# PA_MCU.net
KiCad netlist of a schematic drawn in Altium Designer
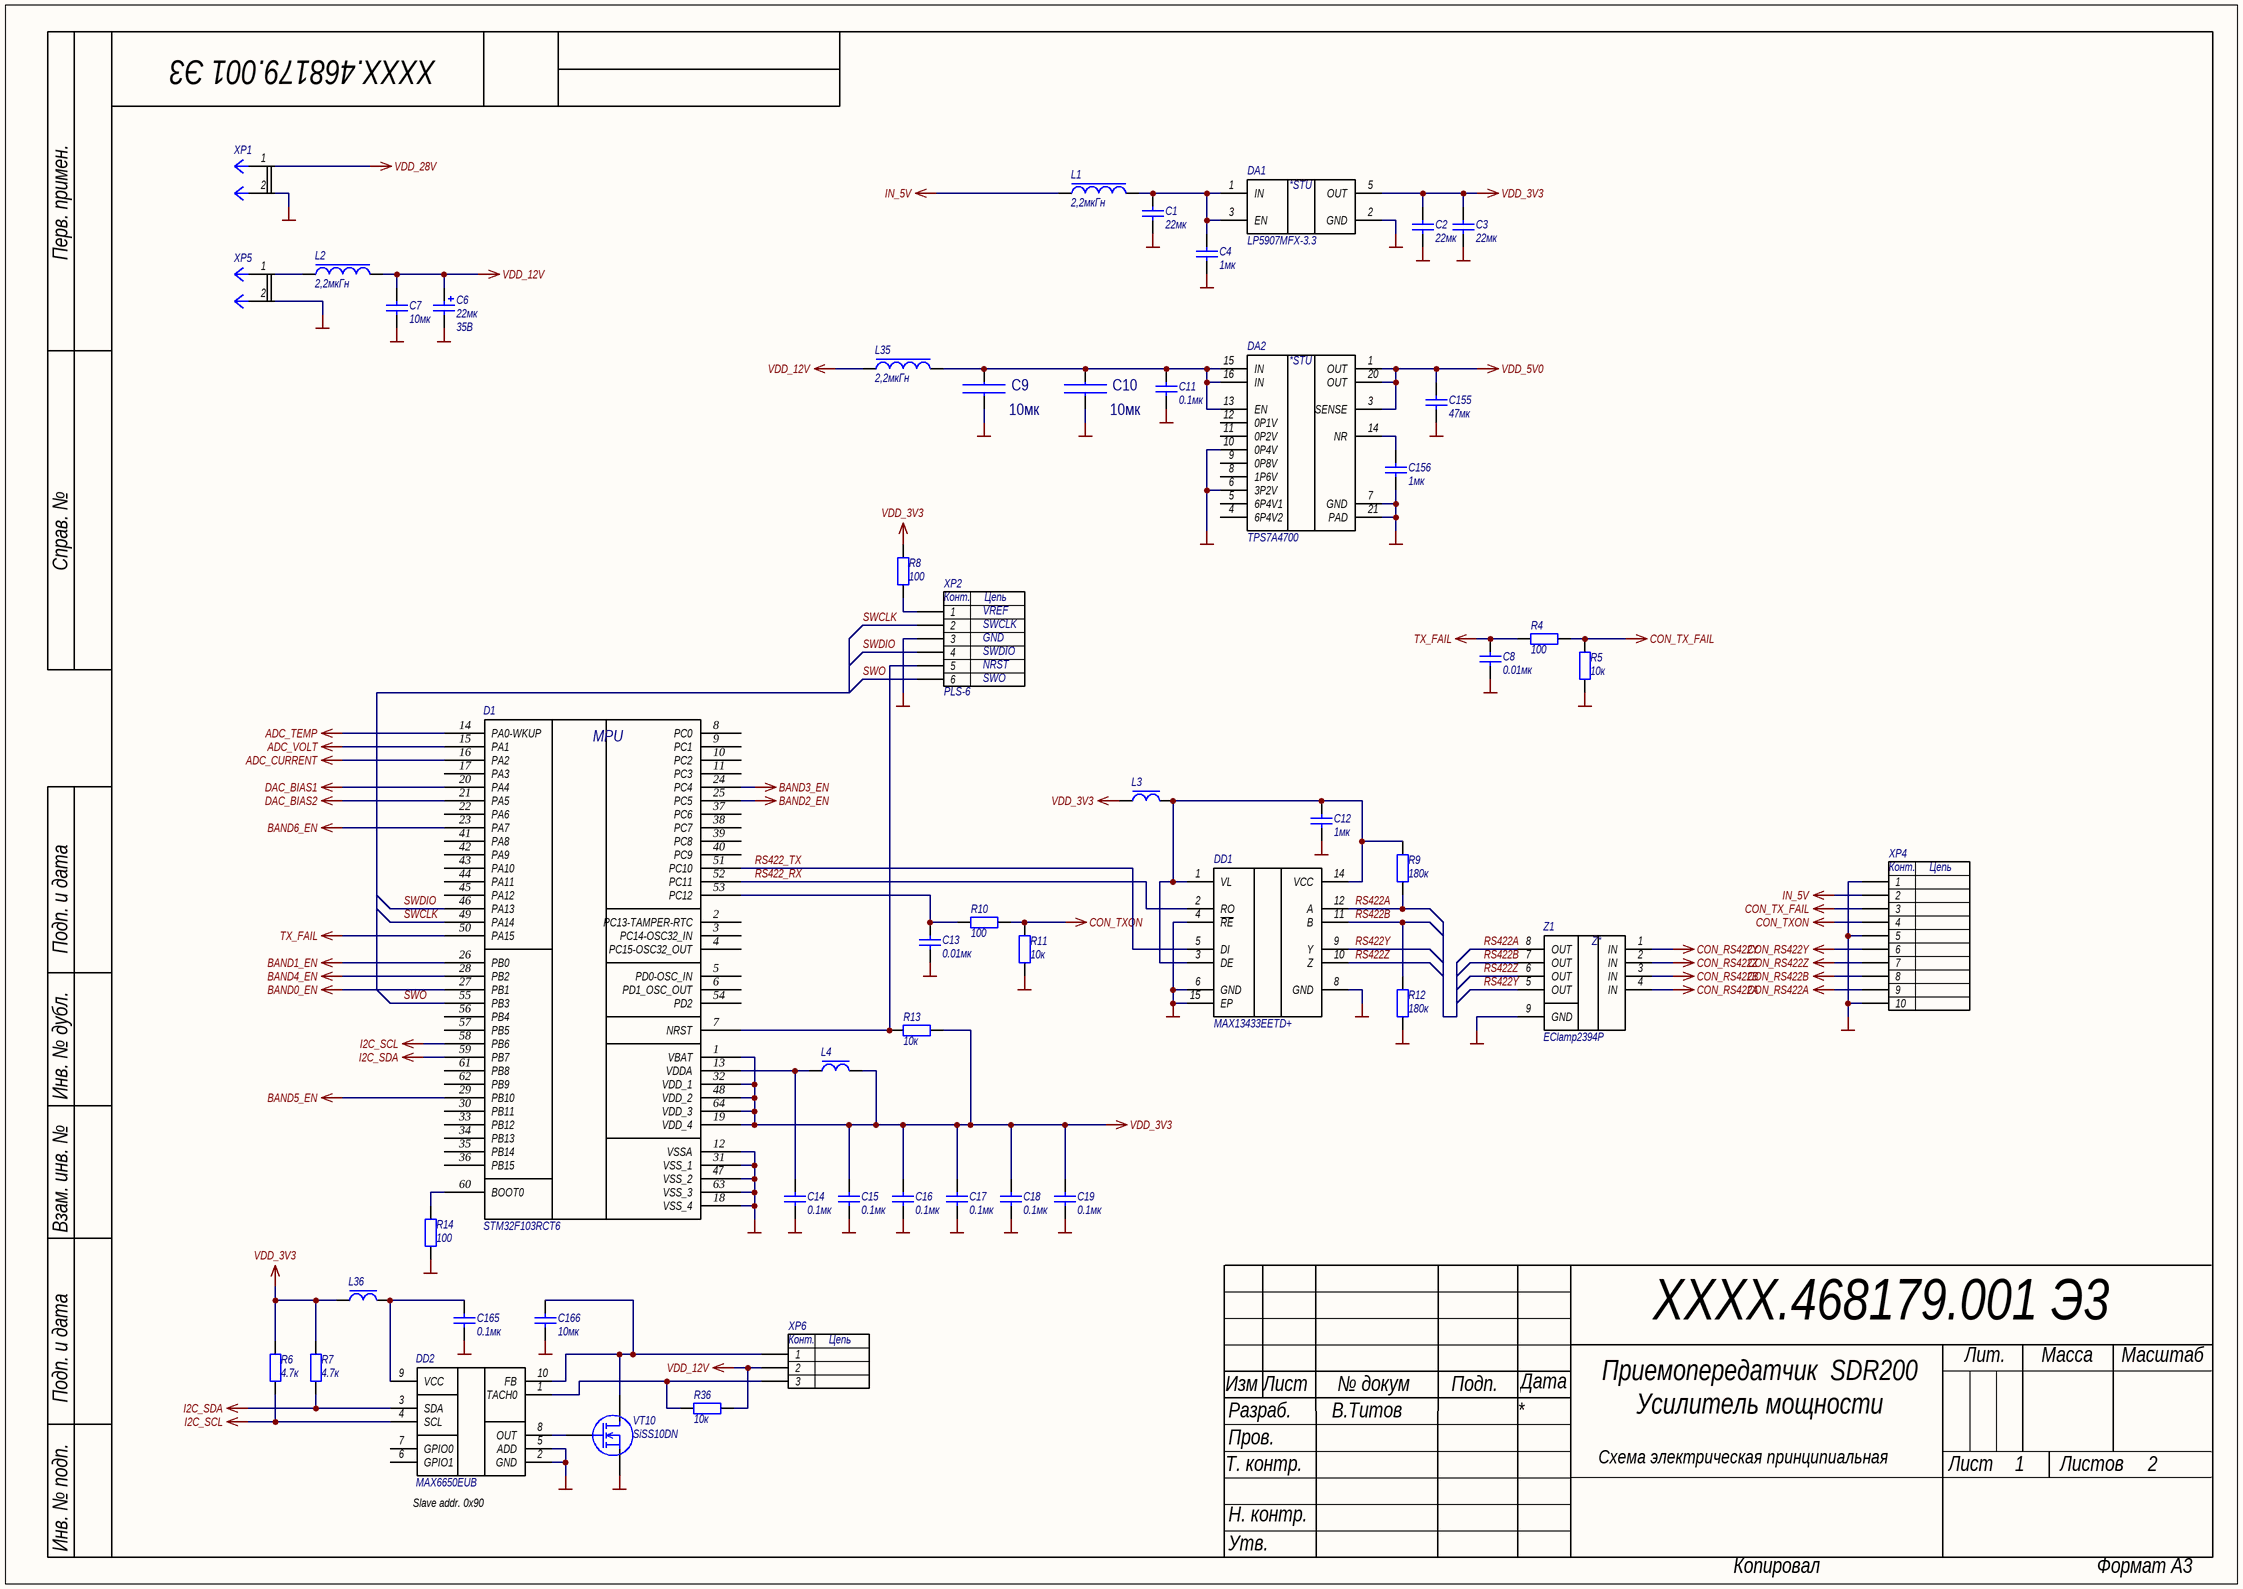
[diagram p0: PA_MCU.SchDoc]

(export (version "E")
  (design (tool "Eeschema 10.0.6"))
  (components
    (comp (ref "C1")
      (value "22мк")
      (footprint "CAPC2012X12L")
      (description "Кер. ЧИП-конденсатор")
      (fields (field (name "MANUFACTURER") "TDK") (field (name "TOLERANCE") "±10%"))
      (libsource (lib "nels_caps") (part "Кер.ЧИП конд. 0805 22мкФ X5R 10% 16В"))
    )
    (comp (ref "C2")
      (value "22мк")
      (footprint "CAPC2012X12L")
      (description "Кер. ЧИП-конденсатор")
      (fields (field (name "MANUFACTURER") "TDK") (field (name "TOLERANCE") "±10%"))
      (libsource (lib "nels_caps") (part "Кер.ЧИП конд. 0805 22мкФ X5R 10% 16В"))
    )
    (comp (ref "C3")
      (value "22мк")
      (footprint "CAPC2012X12L")
      (description "Кер. ЧИП-конденсатор")
      (fields (field (name "MANUFACTURER") "TDK") (field (name "TOLERANCE") "±10%"))
      (libsource (lib "nels_caps") (part "Кер.ЧИП конд. 0805 22мкФ X5R 10% 16В"))
    )
    (comp (ref "C4")
      (value "1мк")
      (footprint "CAPC1005X06N")
      (description "Кер. ЧИП-конденсатор")
      (fields (field (name "TOLERANCE") "±10%"))
      (libsource (lib "nels_caps") (part "Кер.ЧИП конд. 0402 1мкФ X5R 10%, 10В"))
    )
    (comp (ref "C6")
      (value "22мк")
      (footprint "CAPMP7343X28L")
      (description "Тант. ЧИП-конденсатор")
      (fields
        (field (name "TOLERANCE") "±20%")
        (field (name "POWER/VOLTAGE") "35В")
        (field (name "PUBLISHER") "Altium Limited")
      )
      (libsource (lib "nels_caps") (part "Конденсатор танталовый SMD D case 22мкФ ±20% 35B"))
    )
    (comp (ref "C7")
      (value "10мк")
      (footprint "CAPC3225X27L")
      (description "Кер. ЧИП-конденсатор")
      (fields (field (name "MANUFACTURER") "Murata") (field (name "TOLERANCE") "±20%"))
      (libsource (lib "nels_caps") (part "Кер.ЧИП конд. 1210 10мкФ X5R 20% 50В"))
    )
    (comp (ref "C8")
      (value "0.01мк")
      (footprint "CAPC1005X06N")
      (description "Кер. ЧИП-конденсатор")
      (fields (field (name "TOLERANCE") "±20%"))
      (libsource (lib "nels_caps") (part "Кер.ЧИП конд. 0402 0.01мкФ X7R 10%, 50В"))
    )
    (comp (ref "C9")
      (value "CC0805KKX5R8BB106")
      (footprint "CAPC2012X09L")
      (description "ЧИП конденсатор")
      (fields
        (field (name "MANUFACTURER") "Yageo")
        (field (name "TOLERANCE") "0,1")
        (field (name "NOMINAL") "10мк")
      )
      (libsource (lib "Database_Gost") (part "Capacitor const"))
    )
    (comp (ref "C10")
      (value "CC0805KKX5R8BB106")
      (footprint "CAPC2012X09L")
      (description "ЧИП конденсатор")
      (fields
        (field (name "MANUFACTURER") "Yageo")
        (field (name "TOLERANCE") "0,1")
        (field (name "NOMINAL") "10мк")
      )
      (libsource (lib "Database_Gost") (part "Capacitor const"))
    )
    (comp (ref "C11")
      (value "0.1мк")
      (footprint "CAPC1005X06N")
      (description "Кер. ЧИП-конденсатор")
      (fields (field (name "TOLERANCE") "±10%"))
      (libsource (lib "nels") (part "Кер.ЧИП конд. 0402 0.1мкФ X7R 10%, 16В"))
    )
    (comp (ref "C12")
      (value "1мк")
      (footprint "CAPC1005X06N")
      (description "Кер. ЧИП-конденсатор")
      (fields (field (name "TOLERANCE") "±10%"))
      (libsource (lib "nels_caps") (part "Кер.ЧИП конд. 0402 1мкФ X5R 10%, 10В"))
    )
    (comp (ref "C13")
      (value "0.01мк")
      (footprint "CAPC1005X06N")
      (description "Кер. ЧИП-конденсатор")
      (fields (field (name "TOLERANCE") "±20%"))
      (libsource (lib "nels_caps") (part "Кер.ЧИП конд. 0402 0.01мкФ X7R 10%, 50В"))
    )
    (comp (ref "C14")
      (value "0.1мк")
      (footprint "CAPC1005X06N")
      (description "Кер. ЧИП-конденсатор")
      (fields (field (name "TOLERANCE") "±10%"))
      (libsource (lib "nels") (part "Кер.ЧИП конд. 0402 0.1мкФ X7R 10%, 16В"))
    )
    (comp (ref "C15")
      (value "0.1мк")
      (footprint "CAPC1005X06N")
      (description "Кер. ЧИП-конденсатор")
      (fields (field (name "TOLERANCE") "±10%"))
      (libsource (lib "nels") (part "Кер.ЧИП конд. 0402 0.1мкФ X7R 10%, 16В"))
    )
    (comp (ref "C16")
      (value "0.1мк")
      (footprint "CAPC1005X06N")
      (description "Кер. ЧИП-конденсатор")
      (fields (field (name "TOLERANCE") "±10%"))
      (libsource (lib "nels") (part "Кер.ЧИП конд. 0402 0.1мкФ X7R 10%, 16В"))
    )
    (comp (ref "C17")
      (value "0.1мк")
      (footprint "CAPC1005X06N")
      (description "Кер. ЧИП-конденсатор")
      (fields (field (name "TOLERANCE") "±10%"))
      (libsource (lib "nels") (part "Кер.ЧИП конд. 0402 0.1мкФ X7R 10%, 16В"))
    )
    (comp (ref "C18")
      (value "0.1мк")
      (footprint "CAPC1005X06N")
      (description "Кер. ЧИП-конденсатор")
      (fields (field (name "TOLERANCE") "±10%"))
      (libsource (lib "nels") (part "Кер.ЧИП конд. 0402 0.1мкФ X7R 10%, 16В"))
    )
    (comp (ref "C19")
      (value "0.1мк")
      (footprint "CAPC1005X06N")
      (description "Кер. ЧИП-конденсатор")
      (fields (field (name "TOLERANCE") "±10%"))
      (libsource (lib "nels") (part "Кер.ЧИП конд. 0402 0.1мкФ X7R 10%, 16В"))
    )
    (comp (ref "C155")
      (value "47мк")
      (footprint "CAPC2012X12L")
      (description "Кер. ЧИП-конденсатор")
      (fields (field (name "MANUFACTURER") "Murata") (field (name "TOLERANCE") "±20%"))
      (libsource (lib "nels_caps") (part "Кер.ЧИП конд. 0805 47мкФ X5R 20% 10В"))
    )
    (comp (ref "C156")
      (value "1мк")
      (footprint "CAPC1005X06N")
      (description "Кер. ЧИП-конденсатор")
      (fields (field (name "TOLERANCE") "±10%"))
      (libsource (lib "nels_caps") (part "Кер.ЧИП конд. 0402 1мкФ X5R 10%, 10В"))
    )
    (comp (ref "C165")
      (value "0.1мк")
      (footprint "CAPC1005X06N")
      (description "Кер. ЧИП-конденсатор")
      (fields (field (name "TOLERANCE") "±10%"))
      (libsource (lib "nels") (part "Кер.ЧИП конд. 0402 0.1мкФ X7R 10%, 16В"))
    )
    (comp (ref "C166")
      (value "10мк")
      (footprint "CAPC3225X27L")
      (description "Кер. ЧИП-конденсатор")
      (fields (field (name "MANUFACTURER") "Murata") (field (name "TOLERANCE") "±20%"))
      (libsource (lib "nels_caps") (part "Кер.ЧИП конд. 1210 10мкФ X5R 20% 50В"))
    )
    (comp (ref "D1")
      (value "STM32F103RCT6")
      (footprint "QFP50P1200X1200X160-64N")
      (fields (field (name "MANUFACTURER") "STMicroelectronics"))
      (libsource (lib "nels_chip") (part "Микросхема STM32F103RCT6"))
    )
    (comp (ref "DA1")
      (value "LP5907MFX-3.3")
      (footprint "SOT23-5AM")
      (description "250-mA Ultra-Low-Noise, Low-IQ LDO")
      (fields (field (name "MANUFACTURER") "TI"))
      (libsource (lib "nels_chip") (part "Микросхема LP5907MFX-3.3"))
    )
    (comp (ref "DA2")
      (value "TPS7A4700")
      (footprint "QFN65P500X500X100_HS-21L")
      (description "36-V, 1-A, 4-µVRMS, RF LDO Voltage Regulator")
      (fields (field (name "MANUFACTURER") "TI"))
      (libsource (lib "nels_chip") (part "Микросхема TPS7A4700RGW"))
    )
    (comp (ref "DD1")
      (value "MAX13433EETD+")
      (footprint "SON40P300X80_HS-15L")
      (description "RS-422 Transceivers with Low-Voltage Logic Interface 16M")
      (fields (field (name "MANUFACTURER") "Maxim"))
      (libsource (lib "nels_chip") (part "Микросхема MAX13433EETD+"))
    )
    (comp (ref "DD2")
      (value "MAX6650EUB")
      (footprint "TSSOP50P490X110-10N")
      (description "Fan-Speed Regulators and Monitors with SMBus/I2C-Compatible Interface")
      (fields (field (name "MANUFACTURER") "Maxim"))
      (libsource (lib "nels_chip") (part "Микросхема MAX6650EUB"))
    )
    (comp (ref "L1")
      (value "2,2мкГн")
      (footprint "CSAB0420")
      (description "Molding Power Choke")
      (fields
        (field (name "MANUFACTURER") "Vishay")
        (field (name "MANUFACTURERPARTNUMBER") "IHLP1616ABER1R0M11")
      )
      (libsource (lib "nels_ind") (part "ЧИП индуктивность CSAB0420-2R2M"))
    )
    (comp (ref "L2")
      (value "2,2мкГн")
      (footprint "CSAB0420")
      (description "Molding Power Choke")
      (fields
        (field (name "MANUFACTURER") "Vishay")
        (field (name "MANUFACTURERPARTNUMBER") "IHLP1616ABER1R0M11")
      )
      (libsource (lib "nels_ind") (part "ЧИП индуктивность CSAB0420-2R2M"))
    )
    (comp (ref "L3")
      (value "BLM18PG121SN1D")
      (footprint "INDC1608X08L")
      (description "SMD EMI Suppression Filter EMIFIL")
      (fields (field (name "MANUFACTURER") "Murata"))
      (libsource (lib "nels_ind") (part "ЧИП дроссель 0603 BLM18PG121SN1D"))
    )
    (comp (ref "L4")
      (value "BLM18PG121SN1D")
      (footprint "INDC1608X08L")
      (description "SMD EMI Suppression Filter EMIFIL")
      (fields (field (name "MANUFACTURER") "Murata"))
      (libsource (lib "nels_ind") (part "ЧИП дроссель 0603 BLM18PG121SN1D"))
    )
    (comp (ref "L35")
      (value "2,2мкГн")
      (footprint "CSAB0420")
      (description "Molding Power Choke")
      (fields
        (field (name "MANUFACTURER") "Vishay")
        (field (name "MANUFACTURERPARTNUMBER") "IHLP1616ABER1R0M11")
      )
      (libsource (lib "nels_ind") (part "ЧИП индуктивность CSAB0420-2R2M"))
    )
    (comp (ref "L36")
      (value "BLM18PG121SN1D")
      (footprint "INDC1608X08L")
      (description "SMD EMI Suppression Filter EMIFIL")
      (fields (field (name "MANUFACTURER") "Murata"))
      (libsource (lib "nels_ind") (part "ЧИП дроссель 0603 BLM18PG121SN1D"))
    )
    (comp (ref "R4")
      (value "100")
      (footprint "RESC1005X06N")
      (description "ЧИП-резистор")
      (fields (field (name "TOLERANCE") "±5%"))
      (libsource (lib "") (part "Чип резистор 0402 100 Ом, 5%_1"))
    )
    (comp (ref "R5")
      (value "10к")
      (footprint "RESC1005X06N")
      (description "ЧИП-резистор")
      (fields (field (name "TOLERANCE") "±5%"))
      (libsource (lib "nels_res") (part "Чип резистор 0402 10 кОм, 5%"))
    )
    (comp (ref "R6")
      (value "4.7к")
      (footprint "RESC1005X06N")
      (description "ЧИП-резистор")
      (fields (field (name "TOLERANCE") "±5%"))
      (libsource (lib "nels_res") (part "Чип резистор 0402 4,7 кОм, 5%"))
    )
    (comp (ref "R7")
      (value "4.7к")
      (footprint "RESC1005X06N")
      (description "ЧИП-резистор")
      (fields (field (name "TOLERANCE") "±5%"))
      (libsource (lib "nels_res") (part "Чип резистор 0402 4,7 кОм, 5%"))
    )
    (comp (ref "R8")
      (value "100")
      (footprint "RESC1005X06N")
      (description "ЧИП-резистор")
      (fields (field (name "TOLERANCE") "±5%"))
      (libsource (lib "nels_res") (part "Чип резистор 0402 100 Ом, 5%"))
    )
    (comp (ref "R9")
      (value "180к")
      (footprint "RESC1005X06N")
      (description "ЧИП-резистор")
      (fields (field (name "TOLERANCE") "±5%"))
      (libsource (lib "nels") (part "Чип резистор 0402 180 кОм, 5%"))
    )
    (comp (ref "R10")
      (value "100")
      (footprint "RESC1005X06N")
      (description "ЧИП-резистор")
      (fields (field (name "TOLERANCE") "±5%"))
      (libsource (lib "") (part "Чип резистор 0402 100 Ом, 5%_1"))
    )
    (comp (ref "R11")
      (value "10к")
      (footprint "RESC1005X06N")
      (description "ЧИП-резистор")
      (fields (field (name "TOLERANCE") "±5%"))
      (libsource (lib "nels_res") (part "Чип резистор 0402 10 кОм, 5%"))
    )
    (comp (ref "R12")
      (value "180к")
      (footprint "RESC1005X06N")
      (description "ЧИП-резистор")
      (fields (field (name "TOLERANCE") "±5%"))
      (libsource (lib "nels") (part "Чип резистор 0402 180 кОм, 5%"))
    )
    (comp (ref "R13")
      (value "10к")
      (footprint "RESC1005X06N")
      (description "ЧИП-резистор")
      (fields (field (name "TOLERANCE") "±5%"))
      (libsource (lib "") (part "Чип резистор 0402 10 кОм, 5%_1"))
    )
    (comp (ref "R14")
      (value "100")
      (footprint "RESC1005X06N")
      (description "ЧИП-резистор")
      (fields (field (name "TOLERANCE") "±5%"))
      (libsource (lib "nels_res") (part "Чип резистор 0402 100 Ом, 5%"))
    )
    (comp (ref "R36")
      (value "10к")
      (footprint "RESC1005X06N")
      (description "ЧИП-резистор")
      (fields (field (name "TOLERANCE") "±5%"))
      (libsource (lib "") (part "Чип резистор 0402 10 кОм, 5%_1"))
    )
    (comp (ref "VT10")
      (value "SiSS10DN")
      (footprint "PowerPAK_1212-8W")
      (description "N-Channel 40 V (D-S) MOSFET")
      (libsource (lib "nels_other") (part "ЧИП транзистор SiSS10DN"))
    )
    (comp (ref "XP1")
      (value "XT60-F")
      (footprint "XT60-F")
      (description "AMASS XT60-F")
      (libsource (lib "nels_conn") (part "Соединитель XT60-F"))
    )
    (comp (ref "XP2")
      (value "PLS-6")
      (footprint "HDR1X6")
      (description "Вилка штыревая 2.54мм 1x6 прямая тип1")
      (fields (field (name "PUBLISHER") "Altium Limited"))
      (libsource (lib "nels_conn") (part "Соединитель PLS-6"))
    )
    (comp (ref "XP4")
      (value "FH12-10S-0.5SVA")
      (footprint "FH12-10S-0.5SH")
      (description "0.5mm  Pitch FPC/FFC Connector FH12 Series")
      (fields (field (name "MANUFACTURER") "Hirose"))
      (libsource (lib "nels_conn") (part "Соединитель FH12-10S-0.5SVA"))
    )
    (comp (ref "XP5")
      (value "XT30UPB-M")
      (footprint "XT30UPB-M")
      (description "AMASS XT30UPB-M  5 mm")
      (libsource (lib "nels_conn") (part "Соединитель XT30UPB-M"))
    )
    (comp (ref "XP6")
      (value "22232031")
      (footprint "22232031")
      (description "Molex 2,54 мм pitch-3")
      (fields (field (name "MANUFACTURER") "Connfly"))
      (libsource (lib "nels_conn") (part "Соединитель 22232031"))
    )
    (comp (ref "Z1")
      (value "EClamp2394P")
      (footprint "SON50P160X65_HS-9N")
      (description "ESD/EMI Protection  for Color LCD Interfaces")
      (fields (field (name "MANUFACTURER") "SEMTECH"))
      (libsource (lib "nels_other") (part "Фильтр EMI EClamp2394P"))
    )
  )
  (nets
    (net (code "1") (name "/RS422A") (class "Default")
      (node (ref "DD1") (pin "12") (pinfunction "A_12") (pintype "passive"))
      (node (ref "R9") (pin "1") (pinfunction "1_1") (pintype "passive"))
      (node (ref "Z1") (pin "8") (pinfunction "OUT_8") (pintype "passive"))
    )
    (net (code "2") (name "/RS422B") (class "Default")
      (node (ref "DD1") (pin "11") (pinfunction "B_11") (pintype "passive"))
      (node (ref "R12") (pin "2") (pinfunction "2_2") (pintype "passive"))
      (node (ref "Z1") (pin "7") (pinfunction "OUT_7") (pintype "passive"))
    )
    (net (code "3") (name "/RS422Y") (class "Default")
      (node (ref "DD1") (pin "9") (pinfunction "Y_9") (pintype "passive"))
      (node (ref "Z1") (pin "5") (pinfunction "OUT_5") (pintype "passive"))
    )
    (net (code "4") (name "/RS422Z") (class "Default")
      (node (ref "DD1") (pin "10") (pinfunction "Z_10") (pintype "passive"))
      (node (ref "Z1") (pin "6") (pinfunction "OUT_6") (pintype "passive"))
    )
    (net (code "5") (name "/RS422_RX") (class "Default")
      (node (ref "D1") (pin "52") (pinfunction "PC11_52") (pintype "passive"))
      (node (ref "DD1") (pin "2") (pinfunction "RO_2") (pintype "passive"))
    )
    (net (code "6") (name "/RS422_TX") (class "Default")
      (node (ref "D1") (pin "51") (pinfunction "PC10_51") (pintype "passive"))
      (node (ref "DD1") (pin "5") (pinfunction "DI_5") (pintype "passive"))
    )
    (net (code "7") (name "/SWCLK") (class "Default")
      (node (ref "D1") (pin "49") (pinfunction "PA14_49") (pintype "passive"))
      (node (ref "XP2") (pin "2") (pinfunction "2_2") (pintype "passive"))
    )
    (net (code "8") (name "/SWDIO") (class "Default")
      (node (ref "D1") (pin "46") (pinfunction "PA13_46") (pintype "passive"))
      (node (ref "XP2") (pin "4") (pinfunction "4_4") (pintype "passive"))
    )
    (net (code "9") (name "/SWO") (class "Default")
      (node (ref "D1") (pin "55") (pinfunction "PB3_55") (pintype "passive"))
      (node (ref "XP2") (pin "6") (pinfunction "6_6") (pintype "passive"))
    )
    (net (code "10") (name "ADC_CURRENT") (class "Default")
      (node (ref "D1") (pin "16") (pinfunction "PA2_16") (pintype "passive"))
    )
    (net (code "11") (name "ADC_TEMP") (class "Default")
      (node (ref "D1") (pin "14") (pinfunction "PA0-WKUP_14") (pintype "passive"))
    )
    (net (code "12") (name "ADC_VOLT") (class "Default")
      (node (ref "D1") (pin "15") (pinfunction "PA1_15") (pintype "passive"))
    )
    (net (code "13") (name "BAND0_EN") (class "Default")
      (node (ref "D1") (pin "27") (pinfunction "PB1_27") (pintype "passive"))
    )
    (net (code "14") (name "BAND1_EN") (class "Default")
      (node (ref "D1") (pin "26") (pinfunction "PB0_26") (pintype "passive"))
    )
    (net (code "15") (name "BAND2_EN") (class "Default")
      (node (ref "D1") (pin "25") (pinfunction "PC5_25") (pintype "passive"))
    )
    (net (code "16") (name "BAND3_EN") (class "Default")
      (node (ref "D1") (pin "24") (pinfunction "PC4_24") (pintype "passive"))
    )
    (net (code "17") (name "BAND4_EN") (class "Default")
      (node (ref "D1") (pin "28") (pinfunction "PB2_28") (pintype "passive"))
    )
    (net (code "18") (name "BAND5_EN") (class "Default")
      (node (ref "D1") (pin "29") (pinfunction "PB10_29") (pintype "passive"))
    )
    (net (code "19") (name "BAND6_EN") (class "Default")
      (node (ref "D1") (pin "23") (pinfunction "PA7_23") (pintype "passive"))
    )
    (net (code "20") (name "CON_RS422A") (class "Default")
      (node (ref "XP4") (pin "9") (pinfunction "9_9") (pintype "passive"))
      (node (ref "Z1") (pin "4") (pinfunction "IN_4") (pintype "passive"))
    )
    (net (code "21") (name "CON_RS422B") (class "Default")
      (node (ref "XP4") (pin "8") (pinfunction "8_8") (pintype "passive"))
      (node (ref "Z1") (pin "3") (pinfunction "IN_3") (pintype "passive"))
    )
    (net (code "22") (name "CON_RS422Y") (class "Default")
      (node (ref "XP4") (pin "6") (pinfunction "6_6") (pintype "passive"))
      (node (ref "Z1") (pin "1") (pinfunction "IN_1") (pintype "passive"))
    )
    (net (code "23") (name "CON_RS422Z") (class "Default")
      (node (ref "XP4") (pin "7") (pinfunction "7_7") (pintype "passive"))
      (node (ref "Z1") (pin "2") (pinfunction "IN_2") (pintype "passive"))
    )
    (net (code "24") (name "CON_TXON") (class "Default")
      (node (ref "R10") (pin "1") (pinfunction "1_1") (pintype "passive"))
      (node (ref "R11") (pin "1") (pinfunction "1_1") (pintype "passive"))
      (node (ref "XP4") (pin "4") (pinfunction "4_4") (pintype "passive"))
    )
    (net (code "25") (name "CON_TX_FAIL") (class "Default")
      (node (ref "R4") (pin "1") (pinfunction "1_1") (pintype "passive"))
      (node (ref "R5") (pin "1") (pinfunction "1_1") (pintype "passive"))
      (node (ref "XP4") (pin "3") (pinfunction "3_3") (pintype "passive"))
    )
    (net (code "26") (name "DAC_BIAS1") (class "Default")
      (node (ref "D1") (pin "20") (pinfunction "PA4_20") (pintype "passive"))
    )
    (net (code "27") (name "DAC_BIAS2") (class "Default")
      (node (ref "D1") (pin "21") (pinfunction "PA5_21") (pintype "passive"))
    )
    (net (code "28") (name "GND") (class "Default")
      (node (ref "C1") (pin "1") (pinfunction "1_1") (pintype "passive"))
      (node (ref "C11") (pin "1") (pinfunction "1_1") (pintype "passive"))
      (node (ref "C12") (pin "1") (pinfunction "1_1") (pintype "passive"))
      (node (ref "C13") (pin "1") (pinfunction "1_1") (pintype "passive"))
      (node (ref "C14") (pin "1") (pinfunction "1_1") (pintype "passive"))
      (node (ref "C15") (pin "1") (pinfunction "1_1") (pintype "passive"))
      (node (ref "C155") (pin "1") (pinfunction "1_1") (pintype "passive"))
      (node (ref "C156") (pin "1") (pinfunction "1_1") (pintype "passive"))
      (node (ref "C16") (pin "1") (pinfunction "1_1") (pintype "passive"))
      (node (ref "C165") (pin "1") (pinfunction "1_1") (pintype "passive"))
      (node (ref "C166") (pin "1") (pinfunction "1_1") (pintype "passive"))
      (node (ref "C17") (pin "1") (pinfunction "1_1") (pintype "passive"))
      (node (ref "C18") (pin "1") (pinfunction "1_1") (pintype "passive"))
      (node (ref "C19") (pin "1") (pinfunction "1_1") (pintype "passive"))
      (node (ref "C2") (pin "1") (pinfunction "1_1") (pintype "passive"))
      (node (ref "C3") (pin "1") (pinfunction "1_1") (pintype "passive"))
      (node (ref "C4") (pin "1") (pinfunction "1_1") (pintype "passive"))
      (node (ref "C6") (pin "1") (pinfunction "1_1") (pintype "passive"))
      (node (ref "C7") (pin "1") (pinfunction "1_1") (pintype "passive"))
      (node (ref "C8") (pin "1") (pinfunction "1_1") (pintype "passive"))
      (node (ref "D1") (pin "12") (pinfunction "VSSA_12") (pintype "passive"))
      (node (ref "D1") (pin "18") (pinfunction "VSS_4_18") (pintype "passive"))
      (node (ref "D1") (pin "31") (pinfunction "VSS_1_31") (pintype "passive"))
      (node (ref "D1") (pin "47") (pinfunction "VSS_2_47") (pintype "passive"))
      (node (ref "D1") (pin "63") (pinfunction "VSS_3_63") (pintype "passive"))
      (node (ref "DA1") (pin "2") (pinfunction "GND_2") (pintype "passive"))
      (node (ref "DA2") (pin "10") (pinfunction "0P4V_10") (pintype "passive"))
      (node (ref "DA2") (pin "21") (pinfunction "PAD_21") (pintype "passive"))
      (node (ref "DA2") (pin "6") (pinfunction "3P2V_6") (pintype "passive"))
      (node (ref "DA2") (pin "7") (pinfunction "GND_7") (pintype "passive"))
      (node (ref "DD1") (pin "15") (pinfunction "EP_15") (pintype "passive"))
      (node (ref "DD1") (pin "4") (pinfunction "~{RE}_4") (pintype "passive"))
      (node (ref "DD1") (pin "6") (pinfunction "GND_6") (pintype "passive"))
      (node (ref "DD1") (pin "8") (pinfunction "GND_8") (pintype "passive"))
      (node (ref "DD2") (pin "2") (pinfunction "GND_2") (pintype "passive"))
      (node (ref "DD2") (pin "5") (pinfunction "ADD_5") (pintype "passive"))
      (node (ref "R11") (pin "2") (pinfunction "2_2") (pintype "passive"))
      (node (ref "R12") (pin "1") (pinfunction "1_1") (pintype "passive"))
      (node (ref "R14") (pin "2") (pinfunction "2_2") (pintype "passive"))
      (node (ref "R5") (pin "2") (pinfunction "2_2") (pintype "passive"))
      (node (ref "VT10") (pin "S") (pinfunction "S_S") (pintype "passive"))
      (node (ref "XP1") (pin "2") (pinfunction "~_2") (pintype "passive"))
      (node (ref "XP2") (pin "3") (pinfunction "3_3") (pintype "passive"))
      (node (ref "XP4") (pin "1") (pinfunction "1_1") (pintype "passive"))
      (node (ref "XP4") (pin "10") (pinfunction "10_10") (pintype "passive"))
      (node (ref "XP4") (pin "5") (pinfunction "5_5") (pintype "passive"))
      (node (ref "XP5") (pin "2") (pinfunction "~_2") (pintype "passive"))
      (node (ref "Z1") (pin "9") (pinfunction "GND_9") (pintype "passive"))
    )
    (net (code "29") (name "I2C_SCL") (class "Default")
      (node (ref "D1") (pin "58") (pinfunction "PB6_58") (pintype "passive"))
      (node (ref "DD2") (pin "4") (pinfunction "SCL_4") (pintype "passive"))
      (node (ref "R6") (pin "1") (pinfunction "1_1") (pintype "passive"))
    )
    (net (code "30") (name "I2C_SDA") (class "Default")
      (node (ref "D1") (pin "59") (pinfunction "PB7_59") (pintype "passive"))
      (node (ref "DD2") (pin "3") (pinfunction "SDA_3") (pintype "passive"))
      (node (ref "R7") (pin "1") (pinfunction "1_1") (pintype "passive"))
    )
    (net (code "31") (name "IN_5V") (class "Default")
      (node (ref "L1") (pin "1") (pinfunction "1_1") (pintype "passive"))
      (node (ref "XP4") (pin "2") (pinfunction "2_2") (pintype "passive"))
    )
    (net (code "32") (name "Net-(D1-BOOT0)") (class "Default")
      (node (ref "D1") (pin "60") (pinfunction "BOOT0_60") (pintype "passive"))
      (node (ref "R14") (pin "1") (pinfunction "1_1") (pintype "passive"))
    )
    (net (code "33") (name "Net-(D1-NRST)") (class "Default")
      (node (ref "D1") (pin "7") (pinfunction "NRST_7") (pintype "passive"))
      (node (ref "R13") (pin "1") (pinfunction "1_1") (pintype "passive"))
      (node (ref "XP2") (pin "5") (pinfunction "5_5") (pintype "passive"))
    )
    (net (code "34") (name "Net-(D1-PC12)") (class "Default")
      (node (ref "C13") (pin "2") (pinfunction "2_2") (pintype "passive"))
      (node (ref "D1") (pin "53") (pinfunction "PC12_53") (pintype "passive"))
      (node (ref "R10") (pin "2") (pinfunction "2_2") (pintype "passive"))
    )
    (net (code "35") (name "Net-(D1-VDDA)") (class "Default")
      (node (ref "C14") (pin "2") (pinfunction "2_2") (pintype "passive"))
      (node (ref "D1") (pin "13") (pinfunction "VDDA_13") (pintype "passive"))
      (node (ref "L4") (pin "1") (pinfunction "1_1") (pintype "passive"))
    )
    (net (code "36") (name "Net-(DA1-EN)") (class "Default")
      (node (ref "C1") (pin "2") (pinfunction "2_2") (pintype "passive"))
      (node (ref "C4") (pin "2") (pinfunction "2_2") (pintype "passive"))
      (node (ref "DA1") (pin "1") (pinfunction "IN_1") (pintype "passive"))
      (node (ref "DA1") (pin "3") (pinfunction "EN_3") (pintype "passive"))
      (node (ref "L1") (pin "2") (pinfunction "2_2") (pintype "passive"))
    )
    (net (code "37") (name "Net-(DA2-EN)") (class "Default")
      (node (ref "C10") (pin "2") (pinfunction "2_2") (pintype "passive"))
      (node (ref "C11") (pin "2") (pinfunction "2_2") (pintype "passive"))
      (node (ref "C9") (pin "2") (pinfunction "2_2") (pintype "passive"))
      (node (ref "DA2") (pin "13") (pinfunction "EN_13") (pintype "passive"))
      (node (ref "DA2") (pin "15") (pinfunction "IN_15") (pintype "passive"))
      (node (ref "DA2") (pin "16") (pinfunction "IN_16") (pintype "passive"))
      (node (ref "L35") (pin "2") (pinfunction "2_2") (pintype "passive"))
    )
    (net (code "38") (name "Net-(DA2-NR)") (class "Default")
      (node (ref "C156") (pin "2") (pinfunction "2_2") (pintype "passive"))
      (node (ref "DA2") (pin "14") (pinfunction "NR_14") (pintype "passive"))
    )
    (net (code "39") (name "Net-(DD1-DE)") (class "Default")
      (node (ref "C12") (pin "2") (pinfunction "2_2") (pintype "passive"))
      (node (ref "DD1") (pin "1") (pinfunction "VL_1") (pintype "passive"))
      (node (ref "DD1") (pin "14") (pinfunction "VCC_14") (pintype "passive"))
      (node (ref "DD1") (pin "3") (pinfunction "DE_3") (pintype "passive"))
      (node (ref "L3") (pin "2") (pinfunction "2_2") (pintype "passive"))
      (node (ref "R9") (pin "2") (pinfunction "2_2") (pintype "passive"))
    )
    (net (code "40") (name "Net-(DD2-FB)") (class "Default")
      (node (ref "C166") (pin "2") (pinfunction "2_2") (pintype "passive"))
      (node (ref "DD2") (pin "10") (pinfunction "FB_10") (pintype "passive"))
      (node (ref "VT10") (pin "D") (pinfunction "D_D") (pintype "passive"))
      (node (ref "XP6") (pin "1") (pinfunction "1_1") (pintype "passive"))
    )
    (net (code "41") (name "Net-(DD2-OUT)") (class "Default")
      (node (ref "DD2") (pin "8") (pinfunction "OUT_8") (pintype "passive"))
      (node (ref "VT10") (pin "G") (pinfunction "G_G") (pintype "passive"))
    )
    (net (code "42") (name "Net-(DD2-TACH0)") (class "Default")
      (node (ref "DD2") (pin "1") (pinfunction "TACH0_1") (pintype "passive"))
      (node (ref "R36") (pin "1") (pinfunction "1_1") (pintype "passive"))
      (node (ref "XP6") (pin "3") (pinfunction "3_3") (pintype "passive"))
    )
    (net (code "43") (name "Net-(DD2-VCC)") (class "Default")
      (node (ref "C165") (pin "2") (pinfunction "2_2") (pintype "passive"))
      (node (ref "DD2") (pin "9") (pinfunction "VCC_9") (pintype "passive"))
      (node (ref "L36") (pin "2") (pinfunction "2_2") (pintype "passive"))
    )
    (net (code "44") (name "Net-(L2-Pad1)") (class "Default")
      (node (ref "L2") (pin "1") (pinfunction "1_1") (pintype "passive"))
      (node (ref "XP5") (pin "1") (pinfunction "~_1") (pintype "passive"))
    )
    (net (code "45") (name "Net-(R8-Pad2)") (class "Default")
      (node (ref "R8") (pin "2") (pinfunction "2_2") (pintype "passive"))
      (node (ref "XP2") (pin "1") (pinfunction "1_1") (pintype "passive"))
    )
    (net (code "46") (name "TX_FAIL") (class "Default")
      (node (ref "C8") (pin "2") (pinfunction "2_2") (pintype "passive"))
      (node (ref "D1") (pin "50") (pinfunction "PA15_50") (pintype "passive"))
      (node (ref "R4") (pin "2") (pinfunction "2_2") (pintype "passive"))
    )
    (net (code "47") (name "VDD_3V3") (class "Default")
      (node (ref "C15") (pin "2") (pinfunction "2_2") (pintype "passive"))
      (node (ref "C16") (pin "2") (pinfunction "2_2") (pintype "passive"))
      (node (ref "C17") (pin "2") (pinfunction "2_2") (pintype "passive"))
      (node (ref "C18") (pin "2") (pinfunction "2_2") (pintype "passive"))
      (node (ref "C19") (pin "2") (pinfunction "2_2") (pintype "passive"))
      (node (ref "C2") (pin "2") (pinfunction "2_2") (pintype "passive"))
      (node (ref "C3") (pin "2") (pinfunction "2_2") (pintype "passive"))
      (node (ref "D1") (pin "1") (pinfunction "VBAT_1") (pintype "passive"))
      (node (ref "D1") (pin "19") (pinfunction "VDD_4_19") (pintype "passive"))
      (node (ref "D1") (pin "32") (pinfunction "VDD_1_32") (pintype "passive"))
      (node (ref "D1") (pin "48") (pinfunction "VDD_2_48") (pintype "passive"))
      (node (ref "D1") (pin "64") (pinfunction "VDD_3_64") (pintype "passive"))
      (node (ref "DA1") (pin "5") (pinfunction "OUT_5") (pintype "passive"))
      (node (ref "L3") (pin "1") (pinfunction "1_1") (pintype "passive"))
      (node (ref "L36") (pin "1") (pinfunction "1_1") (pintype "passive"))
      (node (ref "L4") (pin "2") (pinfunction "2_2") (pintype "passive"))
      (node (ref "R13") (pin "2") (pinfunction "2_2") (pintype "passive"))
      (node (ref "R6") (pin "2") (pinfunction "2_2") (pintype "passive"))
      (node (ref "R7") (pin "2") (pinfunction "2_2") (pintype "passive"))
      (node (ref "R8") (pin "1") (pinfunction "1_1") (pintype "passive"))
    )
    (net (code "48") (name "VDD_5V0") (class "Default")
      (node (ref "C155") (pin "2") (pinfunction "2_2") (pintype "passive"))
      (node (ref "DA2") (pin "1") (pinfunction "OUT_1") (pintype "passive"))
      (node (ref "DA2") (pin "20") (pinfunction "OUT_20") (pintype "passive"))
      (node (ref "DA2") (pin "3") (pinfunction "SENSE_3") (pintype "passive"))
    )
    (net (code "49") (name "VDD_12V") (class "Default")
      (node (ref "C6") (pin "2") (pinfunction "2_2") (pintype "passive"))
      (node (ref "C7") (pin "2") (pinfunction "2_2") (pintype "passive"))
      (node (ref "L2") (pin "2") (pinfunction "2_2") (pintype "passive"))
      (node (ref "L35") (pin "1") (pinfunction "1_1") (pintype "passive"))
      (node (ref "R36") (pin "2") (pinfunction "2_2") (pintype "passive"))
      (node (ref "XP6") (pin "2") (pinfunction "2_2") (pintype "passive"))
    )
    (net (code "50") (name "VDD_28V") (class "Default")
      (node (ref "XP1") (pin "1") (pinfunction "~_1") (pintype "passive"))
    )
    (net (code "51") (name "unconnected-(C9-Pad1)") (class "Default")
      (node (ref "C9") (pin "1") (pinfunction "1_1") (pintype "passive"))
    )
    (net (code "52") (name "unconnected-(C10-Pad1)") (class "Default")
      (node (ref "C10") (pin "1") (pinfunction "1_1") (pintype "passive"))
    )
    (net (code "53") (name "unconnected-(D1-PA3-Pad17)") (class "Default")
      (node (ref "D1") (pin "17") (pinfunction "PA3_17") (pintype "passive"))
    )
    (net (code "54") (name "unconnected-(D1-PA6-Pad22)") (class "Default")
      (node (ref "D1") (pin "22") (pinfunction "PA6_22") (pintype "passive"))
    )
    (net (code "55") (name "unconnected-(D1-PA8-Pad41)") (class "Default")
      (node (ref "D1") (pin "41") (pinfunction "PA8_41") (pintype "passive"))
    )
    (net (code "56") (name "unconnected-(D1-PA9-Pad42)") (class "Default")
      (node (ref "D1") (pin "42") (pinfunction "PA9_42") (pintype "passive"))
    )
    (net (code "57") (name "unconnected-(D1-PA10-Pad43)") (class "Default")
      (node (ref "D1") (pin "43") (pinfunction "PA10_43") (pintype "passive"))
    )
    (net (code "58") (name "unconnected-(D1-PA11-Pad44)") (class "Default")
      (node (ref "D1") (pin "44") (pinfunction "PA11_44") (pintype "passive"))
    )
    (net (code "59") (name "unconnected-(D1-PA12-Pad45)") (class "Default")
      (node (ref "D1") (pin "45") (pinfunction "PA12_45") (pintype "passive"))
    )
    (net (code "60") (name "unconnected-(D1-PB4-Pad56)") (class "Default")
      (node (ref "D1") (pin "56") (pinfunction "PB4_56") (pintype "passive"))
    )
    (net (code "61") (name "unconnected-(D1-PB5-Pad57)") (class "Default")
      (node (ref "D1") (pin "57") (pinfunction "PB5_57") (pintype "passive"))
    )
    (net (code "62") (name "unconnected-(D1-PB8-Pad61)") (class "Default")
      (node (ref "D1") (pin "61") (pinfunction "PB8_61") (pintype "passive"))
    )
    (net (code "63") (name "unconnected-(D1-PB9-Pad62)") (class "Default")
      (node (ref "D1") (pin "62") (pinfunction "PB9_62") (pintype "passive"))
    )
    (net (code "64") (name "unconnected-(D1-PB11-Pad30)") (class "Default")
      (node (ref "D1") (pin "30") (pinfunction "PB11_30") (pintype "passive"))
    )
    (net (code "65") (name "unconnected-(D1-PB12-Pad33)") (class "Default")
      (node (ref "D1") (pin "33") (pinfunction "PB12_33") (pintype "passive"))
    )
    (net (code "66") (name "unconnected-(D1-PB13-Pad34)") (class "Default")
      (node (ref "D1") (pin "34") (pinfunction "PB13_34") (pintype "passive"))
    )
    (net (code "67") (name "unconnected-(D1-PB14-Pad35)") (class "Default")
      (node (ref "D1") (pin "35") (pinfunction "PB14_35") (pintype "passive"))
    )
    (net (code "68") (name "unconnected-(D1-PB15-Pad36)") (class "Default")
      (node (ref "D1") (pin "36") (pinfunction "PB15_36") (pintype "passive"))
    )
    (net (code "69") (name "unconnected-(D1-PC0-Pad8)") (class "Default")
      (node (ref "D1") (pin "8") (pinfunction "PC0_8") (pintype "passive"))
    )
    (net (code "70") (name "unconnected-(D1-PC1-Pad9)") (class "Default")
      (node (ref "D1") (pin "9") (pinfunction "PC1_9") (pintype "passive"))
    )
    (net (code "71") (name "unconnected-(D1-PC2-Pad10)") (class "Default")
      (node (ref "D1") (pin "10") (pinfunction "PC2_10") (pintype "passive"))
    )
    (net (code "72") (name "unconnected-(D1-PC3-Pad11)") (class "Default")
      (node (ref "D1") (pin "11") (pinfunction "PC3_11") (pintype "passive"))
    )
    (net (code "73") (name "unconnected-(D1-PC6-Pad37)") (class "Default")
      (node (ref "D1") (pin "37") (pinfunction "PC6_37") (pintype "passive"))
    )
    (net (code "74") (name "unconnected-(D1-PC7-Pad38)") (class "Default")
      (node (ref "D1") (pin "38") (pinfunction "PC7_38") (pintype "passive"))
    )
    (net (code "75") (name "unconnected-(D1-PC8-Pad39)") (class "Default")
      (node (ref "D1") (pin "39") (pinfunction "PC8_39") (pintype "passive"))
    )
    (net (code "76") (name "unconnected-(D1-PC9-Pad40)") (class "Default")
      (node (ref "D1") (pin "40") (pinfunction "PC9_40") (pintype "passive"))
    )
    (net (code "77") (name "unconnected-(D1-PC13-TAMPER-RTC-Pad2)") (class "Default")
      (node (ref "D1") (pin "2") (pinfunction "PC13-TAMPER-RTC_2") (pintype "passive"))
    )
    (net (code "78") (name "unconnected-(D1-PC14-OSC32_IN-Pad3)") (class "Default")
      (node (ref "D1") (pin "3") (pinfunction "PC14-OSC32_IN_3") (pintype "passive"))
    )
    (net (code "79") (name "unconnected-(D1-PC15-OSC32_OUT-Pad4)") (class "Default")
      (node (ref "D1") (pin "4") (pinfunction "PC15-OSC32_OUT_4") (pintype "passive"))
    )
    (net (code "80") (name "unconnected-(D1-PD0-OSC_IN-Pad5)") (class "Default")
      (node (ref "D1") (pin "5") (pinfunction "PD0-OSC_IN_5") (pintype "passive"))
    )
    (net (code "81") (name "unconnected-(D1-PD1_OSC_OUT-Pad6)") (class "Default")
      (node (ref "D1") (pin "6") (pinfunction "PD1_OSC_OUT_6") (pintype "passive"))
    )
    (net (code "82") (name "unconnected-(D1-PD2-Pad54)") (class "Default")
      (node (ref "D1") (pin "54") (pinfunction "PD2_54") (pintype "passive"))
    )
    (net (code "83") (name "unconnected-(DA2-0P1V-Pad12)") (class "Default")
      (node (ref "DA2") (pin "12") (pinfunction "0P1V_12") (pintype "passive"))
    )
    (net (code "84") (name "unconnected-(DA2-0P2V-Pad11)") (class "Default")
      (node (ref "DA2") (pin "11") (pinfunction "0P2V_11") (pintype "passive"))
    )
    (net (code "85") (name "unconnected-(DA2-0P8V-Pad9)") (class "Default")
      (node (ref "DA2") (pin "9") (pinfunction "0P8V_9") (pintype "passive"))
    )
    (net (code "86") (name "unconnected-(DA2-1P6V-Pad8)") (class "Default")
      (node (ref "DA2") (pin "8") (pinfunction "1P6V_8") (pintype "passive"))
    )
    (net (code "87") (name "unconnected-(DA2-6P4V1-Pad5)") (class "Default")
      (node (ref "DA2") (pin "5") (pinfunction "6P4V1_5") (pintype "passive"))
    )
    (net (code "88") (name "unconnected-(DA2-6P4V2-Pad4)") (class "Default")
      (node (ref "DA2") (pin "4") (pinfunction "6P4V2_4") (pintype "passive"))
    )
    (net (code "89") (name "unconnected-(DD2-GPIO0-Pad7)") (class "Default")
      (node (ref "DD2") (pin "7") (pinfunction "GPIO0_7") (pintype "passive"))
    )
    (net (code "90") (name "unconnected-(DD2-GPIO1-Pad6)") (class "Default")
      (node (ref "DD2") (pin "6") (pinfunction "GPIO1_6") (pintype "passive"))
    )
  )
)
